# EMI_SHIELD.net
KiCad netlist of a schematic drawn in EAGLE
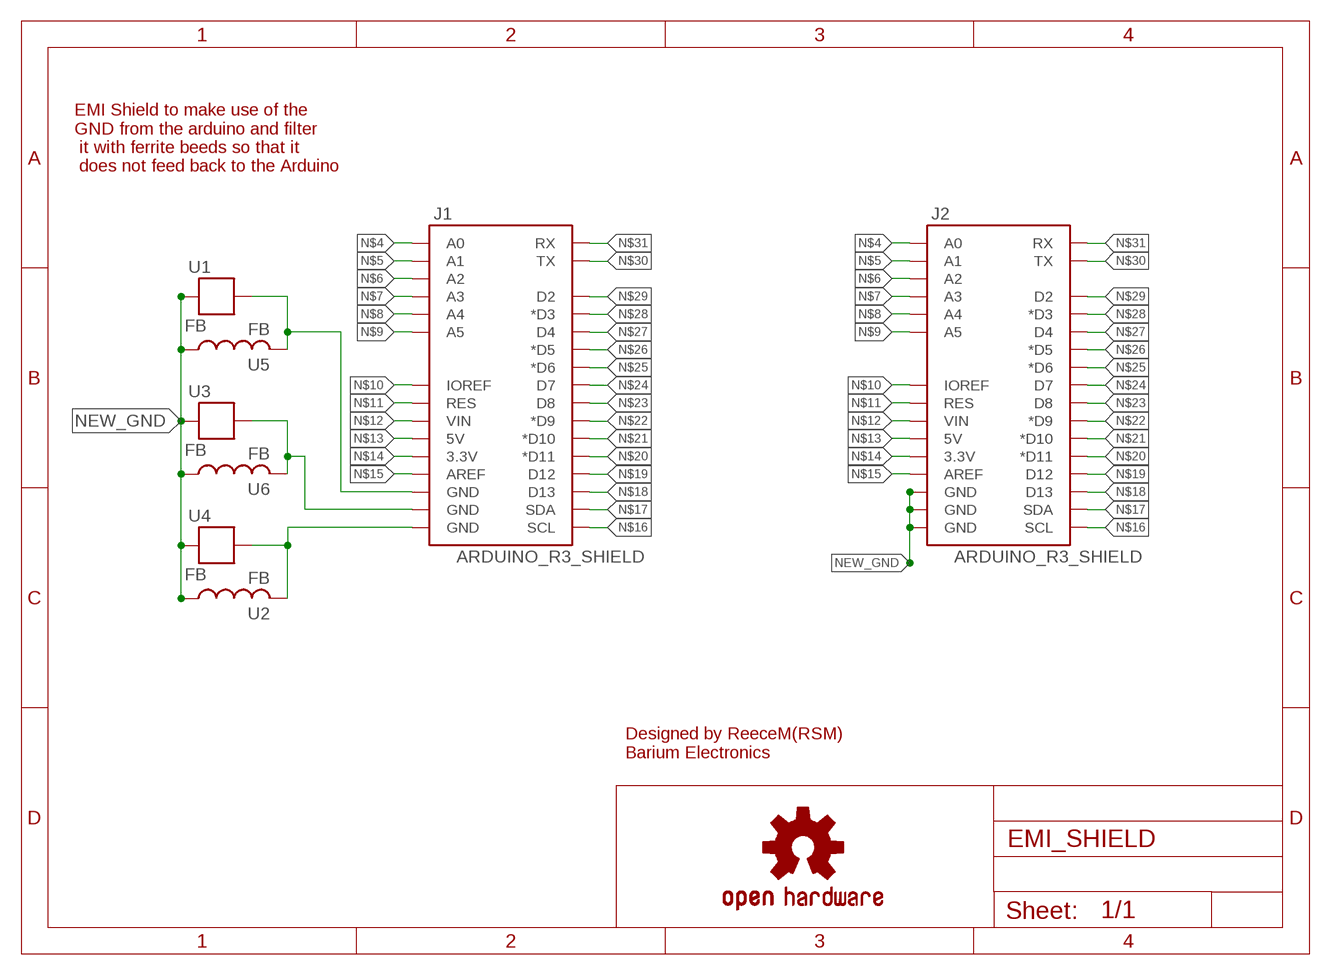
[diagram p0: schematic, sheet 1]

(export (version "E")
  (design (tool "Eeschema 10.0.6"))
  (components
    (comp (ref "J1")
      (value "ARDUINO_R3_SHIELD")
      (footprint "eagle-import:UNO_R3_SHIELD")
      (libsource (lib "eagle-import") (part "ARDUINO_R3_SHIELD"))
    )
    (comp (ref "J2")
      (value "ARDUINO_R3_SHIELD")
      (footprint "eagle-import:UNO_R3_SHIELD")
      (libsource (lib "eagle-import") (part "ARDUINO_R3_SHIELD"))
    )
    (comp (ref "LOGO1")
      (value "OSHW-LOGOM-COPPER")
      (footprint "eagle-import:OSHW-LOGO-M_COPPER")
      (libsource (lib "eagle-import") (part "OSHW-LOGOM-COPPER"))
    )
    (comp (ref "U1")
      (value "FB")
      (footprint "eagle-import:0603")
      (libsource (lib "eagle-import") (part "FB"))
    )
    (comp (ref "U2")
      (value "FB")
      (footprint "eagle-import:FB")
      (libsource (lib "eagle-import") (part "adafruit_FB"))
    )
    (comp (ref "U3")
      (value "FB")
      (footprint "eagle-import:0603")
      (libsource (lib "eagle-import") (part "FB"))
    )
    (comp (ref "U4")
      (value "FB")
      (footprint "eagle-import:0603")
      (libsource (lib "eagle-import") (part "FB"))
    )
    (comp (ref "U5")
      (value "FB")
      (footprint "eagle-import:FB")
      (libsource (lib "eagle-import") (part "adafruit_FB"))
    )
    (comp (ref "U6")
      (value "FB")
      (footprint "eagle-import:FB")
      (libsource (lib "eagle-import") (part "adafruit_FB"))
    )
  )
  (nets
    (net (code "1") (name "N$4") (class "Default")
      (node (ref "J1") (pin "A0") (pinfunction "A0_A0") (pintype "bidirectional"))
      (node (ref "J2") (pin "A0") (pinfunction "A0_A0") (pintype "bidirectional"))
    )
    (net (code "2") (name "N$5") (class "Default")
      (node (ref "J1") (pin "A1") (pinfunction "A1_A1") (pintype "bidirectional"))
      (node (ref "J2") (pin "A1") (pinfunction "A1_A1") (pintype "bidirectional"))
    )
    (net (code "3") (name "N$6") (class "Default")
      (node (ref "J1") (pin "A2") (pinfunction "A2_A2") (pintype "bidirectional"))
      (node (ref "J2") (pin "A2") (pinfunction "A2_A2") (pintype "bidirectional"))
    )
    (net (code "4") (name "N$7") (class "Default")
      (node (ref "J1") (pin "A3") (pinfunction "A3_A3") (pintype "bidirectional"))
      (node (ref "J2") (pin "A3") (pinfunction "A3_A3") (pintype "bidirectional"))
    )
    (net (code "5") (name "N$8") (class "Default")
      (node (ref "J1") (pin "A4") (pinfunction "A4_A4") (pintype "bidirectional"))
      (node (ref "J2") (pin "A4") (pinfunction "A4_A4") (pintype "bidirectional"))
    )
    (net (code "6") (name "N$9") (class "Default")
      (node (ref "J1") (pin "A5") (pinfunction "A5_A5") (pintype "bidirectional"))
      (node (ref "J2") (pin "A5") (pinfunction "A5_A5") (pintype "bidirectional"))
    )
    (net (code "7") (name "N$10") (class "Default")
      (node (ref "J1") (pin "IOREF") (pinfunction "IOREF_IOREF") (pintype "bidirectional"))
      (node (ref "J2") (pin "IOREF") (pinfunction "IOREF_IOREF") (pintype "bidirectional"))
    )
    (net (code "8") (name "N$11") (class "Default")
      (node (ref "J1") (pin "RES") (pinfunction "RES_RES") (pintype "bidirectional"))
      (node (ref "J2") (pin "RES") (pinfunction "RES_RES") (pintype "bidirectional"))
    )
    (net (code "9") (name "N$12") (class "Default")
      (node (ref "J1") (pin "VIN") (pinfunction "VIN_VIN") (pintype "bidirectional"))
      (node (ref "J2") (pin "VIN") (pinfunction "VIN_VIN") (pintype "bidirectional"))
    )
    (net (code "10") (name "N$13") (class "Default")
      (node (ref "J1") (pin "5V") (pinfunction "5V_5V") (pintype "bidirectional"))
      (node (ref "J2") (pin "5V") (pinfunction "5V_5V") (pintype "bidirectional"))
    )
    (net (code "11") (name "N$14") (class "Default")
      (node (ref "J1") (pin "3.3V") (pinfunction "3.3V_3.3V") (pintype "bidirectional"))
      (node (ref "J2") (pin "3.3V") (pinfunction "3.3V_3.3V") (pintype "bidirectional"))
    )
    (net (code "12") (name "N$15") (class "Default")
      (node (ref "J1") (pin "AREF") (pinfunction "AREF_AREF") (pintype "bidirectional"))
      (node (ref "J2") (pin "AREF") (pinfunction "AREF_AREF") (pintype "bidirectional"))
    )
    (net (code "13") (name "N$16") (class "Default")
      (node (ref "J1") (pin "SCL") (pinfunction "SCL_SCL") (pintype "bidirectional"))
      (node (ref "J2") (pin "SCL") (pinfunction "SCL_SCL") (pintype "bidirectional"))
    )
    (net (code "14") (name "N$17") (class "Default")
      (node (ref "J1") (pin "SDA") (pinfunction "SDA_SDA") (pintype "bidirectional"))
      (node (ref "J2") (pin "SDA") (pinfunction "SDA_SDA") (pintype "bidirectional"))
    )
    (net (code "15") (name "N$18") (class "Default")
      (node (ref "J1") (pin "D13") (pinfunction "D13_D13") (pintype "bidirectional"))
      (node (ref "J2") (pin "D13") (pinfunction "D13_D13") (pintype "bidirectional"))
    )
    (net (code "16") (name "N$19") (class "Default")
      (node (ref "J1") (pin "D12") (pinfunction "D12_D12") (pintype "bidirectional"))
      (node (ref "J2") (pin "D12") (pinfunction "D12_D12") (pintype "bidirectional"))
    )
    (net (code "17") (name "N$20") (class "Default")
      (node (ref "J1") (pin "D11") (pinfunction "*D11_D11") (pintype "bidirectional"))
      (node (ref "J2") (pin "D11") (pinfunction "*D11_D11") (pintype "bidirectional"))
    )
    (net (code "18") (name "N$21") (class "Default")
      (node (ref "J1") (pin "D10") (pinfunction "*D10_D10") (pintype "bidirectional"))
      (node (ref "J2") (pin "D10") (pinfunction "*D10_D10") (pintype "bidirectional"))
    )
    (net (code "19") (name "N$22") (class "Default")
      (node (ref "J1") (pin "D9") (pinfunction "*D9_D9") (pintype "bidirectional"))
      (node (ref "J2") (pin "D9") (pinfunction "*D9_D9") (pintype "bidirectional"))
    )
    (net (code "20") (name "N$23") (class "Default")
      (node (ref "J1") (pin "D8") (pinfunction "D8_D8") (pintype "bidirectional"))
      (node (ref "J2") (pin "D8") (pinfunction "D8_D8") (pintype "bidirectional"))
    )
    (net (code "21") (name "N$24") (class "Default")
      (node (ref "J1") (pin "D7") (pinfunction "D7_D7") (pintype "bidirectional"))
      (node (ref "J2") (pin "D7") (pinfunction "D7_D7") (pintype "bidirectional"))
    )
    (net (code "22") (name "N$25") (class "Default")
      (node (ref "J1") (pin "D6") (pinfunction "*D6_D6") (pintype "bidirectional"))
      (node (ref "J2") (pin "D6") (pinfunction "*D6_D6") (pintype "bidirectional"))
    )
    (net (code "23") (name "N$26") (class "Default")
      (node (ref "J1") (pin "D5") (pinfunction "*D5_D5") (pintype "bidirectional"))
      (node (ref "J2") (pin "D5") (pinfunction "*D5_D5") (pintype "bidirectional"))
    )
    (net (code "24") (name "N$27") (class "Default")
      (node (ref "J1") (pin "D4") (pinfunction "D4_D4") (pintype "bidirectional"))
      (node (ref "J2") (pin "D4") (pinfunction "D4_D4") (pintype "bidirectional"))
    )
    (net (code "25") (name "N$28") (class "Default")
      (node (ref "J1") (pin "D3") (pinfunction "*D3_D3") (pintype "bidirectional"))
      (node (ref "J2") (pin "D3") (pinfunction "*D3_D3") (pintype "bidirectional"))
    )
    (net (code "26") (name "N$29") (class "Default")
      (node (ref "J1") (pin "D2") (pinfunction "D2_D2") (pintype "bidirectional"))
      (node (ref "J2") (pin "D2") (pinfunction "D2_D2") (pintype "bidirectional"))
    )
    (net (code "27") (name "N$30") (class "Default")
      (node (ref "J1") (pin "TX") (pinfunction "TX_TX") (pintype "bidirectional"))
      (node (ref "J2") (pin "TX") (pinfunction "TX_TX") (pintype "bidirectional"))
    )
    (net (code "28") (name "N$31") (class "Default")
      (node (ref "J1") (pin "RX") (pinfunction "RX_RX") (pintype "bidirectional"))
      (node (ref "J2") (pin "RX") (pinfunction "RX_RX") (pintype "bidirectional"))
    )
    (net (code "29") (name "NEW_GND") (class "Default")
      (node (ref "J2") (pin "GND@0") (pinfunction "GND_GND@0") (pintype "bidirectional"))
      (node (ref "J2") (pin "GND@1") (pinfunction "GND_GND@1") (pintype "bidirectional"))
      (node (ref "J2") (pin "GND@2") (pinfunction "GND_GND@2") (pintype "bidirectional"))
      (node (ref "U1") (pin "2") (pinfunction "P$2_2") (pintype "bidirectional"))
      (node (ref "U2") (pin "P$1") (pinfunction "1_P$1") (pintype "passive"))
      (node (ref "U3") (pin "2") (pinfunction "P$2_2") (pintype "bidirectional"))
      (node (ref "U4") (pin "2") (pinfunction "P$2_2") (pintype "bidirectional"))
      (node (ref "U5") (pin "P$1") (pinfunction "1_P$1") (pintype "passive"))
      (node (ref "U6") (pin "P$1") (pinfunction "1_P$1") (pintype "passive"))
    )
    (net (code "30") (name "Net-(U1-P$1)") (class "Default")
      (node (ref "J1") (pin "GND@2") (pinfunction "GND_GND@2") (pintype "bidirectional"))
      (node (ref "U1") (pin "1") (pinfunction "P$1_1") (pintype "bidirectional"))
      (node (ref "U5") (pin "P$2") (pinfunction "2_P$2") (pintype "passive"))
    )
    (net (code "31") (name "Net-(U2-2)") (class "Default")
      (node (ref "J1") (pin "GND@0") (pinfunction "GND_GND@0") (pintype "bidirectional"))
      (node (ref "U2") (pin "P$2") (pinfunction "2_P$2") (pintype "passive"))
      (node (ref "U4") (pin "1") (pinfunction "P$1_1") (pintype "bidirectional"))
    )
    (net (code "32") (name "Net-(U3-P$1)") (class "Default")
      (node (ref "J1") (pin "GND@1") (pinfunction "GND_GND@1") (pintype "bidirectional"))
      (node (ref "U3") (pin "1") (pinfunction "P$1_1") (pintype "bidirectional"))
      (node (ref "U6") (pin "P$2") (pinfunction "2_P$2") (pintype "passive"))
    )
  )
)
